# 02_Power.net
KiCad netlist of a schematic drawn in Altium Designer
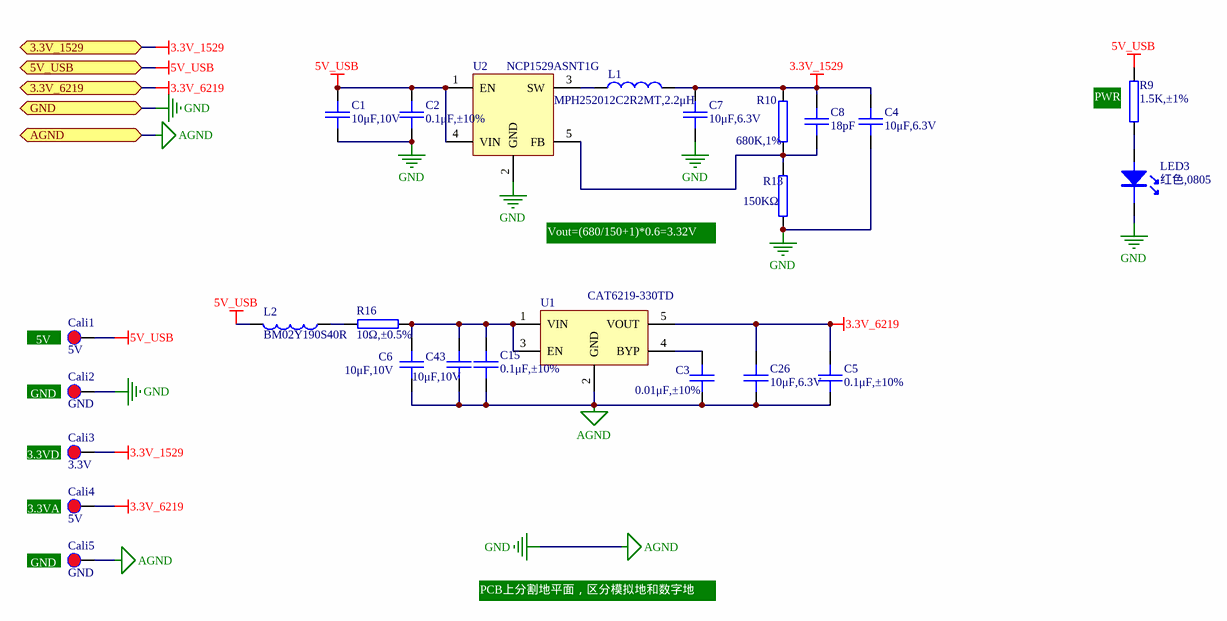
[diagram p0: 02.Power.SchDoc]

(export (version "E")
  (design (tool "Eeschema 10.0.6"))
  (components
    (comp (ref "C1")
      (value "10μF,10V")
      (footprint "0805C")
      (description "10μF,±10%,10V,X7R,GRM21BR71A106KE51L,0805,muRata,RoHS")
      (libsource (lib "ErpMaterialData") (part "CAP1"))
    )
    (comp (ref "C2")
      (value "0.1μF,±10%")
      (footprint "0402C")
      (description "GRM155R71C104KA88D,0.1μF,±10%,16V,X7R,0402,muRata,RoHS")
      (libsource (lib "ErpMaterialData") (part "CAP1"))
    )
    (comp (ref "C3")
      (value "0.01μF,±10%")
      (footprint "0402C")
      (description "GRM155R71H103KA88D,0.01μF,±10%,50V,X7R,0402,muRata,RoHS")
      (libsource (lib "ErpMaterialData") (part "CAP1"))
    )
    (comp (ref "C4")
      (value "10μF,6.3V")
      (footprint "0603C")
      (description "10μF,6.3V,X5R,GRM188R60J106M****,0603,Murata,RoHS")
      (libsource (lib "ErpMaterialData") (part "CAP1"))
    )
    (comp (ref "C5")
      (value "0.1μF,±10%")
      (footprint "0402C")
      (description "GRM155R71C104KA88D,0.1μF,±10%,16V,X7R,0402,muRata,RoHS")
      (libsource (lib "ErpMaterialData") (part "CAP1"))
    )
    (comp (ref "C6")
      (value "10μF,10V")
      (footprint "0805C")
      (description "10μF,±10%,10V,X7R,GRM21BR71A106KE51L,0805,muRata,RoHS")
      (libsource (lib "ErpMaterialData") (part "CAP1"))
    )
    (comp (ref "C7")
      (value "10μF,6.3V")
      (footprint "0603C")
      (description "10μF,6.3V,X5R,GRM188R60J106M****,0603,Murata,RoHS")
      (libsource (lib "ErpMaterialData") (part "CAP1"))
    )
    (comp (ref "C8")
      (value "18pF")
      (footprint "0402C")
      (description "GRM1555C1H180JA01D,18pF,±5%,50V,C0G,0402,muRata,RoHS")
      (libsource (lib "ErpMaterialData") (part "CAP1"))
    )
    (comp (ref "C15")
      (value "0.1μF,±10%")
      (footprint "0402C")
      (description "GRM155R71C104KA88D,0.1μF,±10%,16V,X7R,0402,muRata,RoHS")
      (libsource (lib "ErpMaterialData") (part "CAP1"))
    )
    (comp (ref "C26")
      (value "10μF,6.3V")
      (footprint "0603C")
      (description "10μF,6.3V,X5R,GRM188R60J106M****,0603,Murata,RoHS")
      (libsource (lib "ErpMaterialData") (part "CAP1"))
    )
    (comp (ref "C43")
      (value "10μF,10V")
      (footprint "0805C")
      (description "10μF,±10%,10V,X7R,GRM21BR71A106KE51L,0805,muRata,RoHS")
      (libsource (lib "ErpMaterialData") (part "CAP1"))
    )
    (comp (ref "Cali1") (value "5V") (footprint "PAD-25/40") (libsource (lib "无需物料号元件") (part "TEST-DOT")))
    (comp (ref "Cali2") (value "GND") (footprint "PAD-25/40") (libsource (lib "无需物料号元件") (part "TEST-DOT")))
    (comp (ref "Cali3") (value "3.3V") (footprint "PAD-25/40") (libsource (lib "无需物料号元件") (part "TEST-DOT")))
    (comp (ref "Cali4") (value "5V") (footprint "PAD-25/40") (libsource (lib "无需物料号元件") (part "TEST-DOT")))
    (comp (ref "Cali5") (value "GND") (footprint "PAD-25/40") (libsource (lib "无需物料号元件") (part "TEST-DOT")))
    (comp (ref "L1")
      (value "MPH252012C2R2MT,2.2μH")
      (footprint "INDC2520X10N")
      (description "MPH252012C2R2MT,2.2μH,±20%,700mA,1008,Sunlord,RoHs")
      (libsource (lib "ErpMaterialData") (part "INDUCTOR1"))
    )
    (comp (ref "L2")
      (value "BM02Y190S40R")
      (footprint "0402RL")
      (description "BM02Y190S40R,0402,丰晶,RoHS")
      (libsource (lib "ErpMaterialData") (part "INDUCTOR1"))
    )
    (comp (ref "LED3")
      (value "红色,0805")
      (footprint "LED-0805")
      (description "红色,0805,0805,RoHS")
      (fields (field (name "Comment") "LED1"))
      (libsource (lib "ErpMaterialData") (part "LED1"))
    )
    (comp (ref "R9")
      (value "1.5K,±1%")
      (footprint "0402R")
      (description "1.5K,±1%,0402,RALEC,RoHS")
      (libsource (lib "ErpMaterialData") (part "RES2"))
    )
    (comp (ref "R10")
      (value "680K,1%")
      (footprint "0402R")
      (description "680K,1%,0402,Ralec,RoHS")
      (libsource (lib "ErpMaterialData") (part "RES2"))
    )
    (comp (ref "R13")
      (value "150KΩ")
      (footprint "0603R")
      (description "150KΩ,0603,*,RoHS")
      (libsource (lib "ErpMaterialData") (part "RES2"))
    )
    (comp (ref "R16")
      (value "10Ω,±0.5%")
      (footprint "0402R")
      (description "10Ω,±0.5%,0402,RoHS")
      (libsource (lib "ErpMaterialData") (part "RES2"))
    )
    (comp (ref "U1")
      (value "CAT6219-330TD")
      (footprint "SOT-23-5")
      (description "CAT6219-330TD,TSOT-23-5,ON,RoHS")
      (libsource (lib "ErpMaterialData") (part "CAT6219"))
    )
    (comp (ref "U2")
      (value "NCP1529ASNT1G")
      (footprint "SOT-23-5")
      (description "NCP1529ASNT1G,TSOP-5,ON,RoHS")
      (libsource (lib "ErpMaterialData") (part "SCY99090SNT1G"))
    )
  )
  (nets
    (net (code "1") (name "3.3V_1529") (class "Default")
      (node (ref "C4") (pin "1") (pinfunction "1_1") (pintype "passive"))
      (node (ref "C7") (pin "1") (pinfunction "1_1") (pintype "passive"))
      (node (ref "C8") (pin "1") (pinfunction "1_1") (pintype "passive"))
      (node (ref "Cali3") (pin "1") (pinfunction "1_1") (pintype "passive"))
      (node (ref "L1") (pin "2") (pinfunction "2_2") (pintype "passive"))
      (node (ref "R10") (pin "2") (pinfunction "2_2") (pintype "passive"))
    )
    (net (code "2") (name "3.3V_6219") (class "Default")
      (node (ref "C26") (pin "1") (pinfunction "1_1") (pintype "passive"))
      (node (ref "C5") (pin "1") (pinfunction "1_1") (pintype "passive"))
      (node (ref "Cali4") (pin "1") (pinfunction "1_1") (pintype "passive"))
      (node (ref "U1") (pin "5") (pinfunction "VOUT_5") (pintype "passive"))
    )
    (net (code "3") (name "5V_USB") (class "Default")
      (node (ref "C1") (pin "1") (pinfunction "1_1") (pintype "passive"))
      (node (ref "C2") (pin "1") (pinfunction "1_1") (pintype "passive"))
      (node (ref "Cali1") (pin "1") (pinfunction "1_1") (pintype "passive"))
      (node (ref "L2") (pin "2") (pinfunction "2_2") (pintype "passive"))
      (node (ref "R9") (pin "2") (pinfunction "2_2") (pintype "passive"))
      (node (ref "U2") (pin "1") (pinfunction "EN_1") (pintype "passive"))
      (node (ref "U2") (pin "4") (pinfunction "VIN_4") (pintype "passive"))
    )
    (net (code "4") (name "AGND") (class "Default")
      (node (ref "C1") (pin "2") (pinfunction "2_2") (pintype "passive"))
      (node (ref "C15") (pin "2") (pinfunction "2_2") (pintype "passive"))
      (node (ref "C2") (pin "2") (pinfunction "2_2") (pintype "passive"))
      (node (ref "C26") (pin "2") (pinfunction "2_2") (pintype "passive"))
      (node (ref "C3") (pin "2") (pinfunction "2_2") (pintype "passive"))
      (node (ref "C4") (pin "2") (pinfunction "2_2") (pintype "passive"))
      (node (ref "C43") (pin "2") (pinfunction "2_2") (pintype "passive"))
      (node (ref "C5") (pin "2") (pinfunction "2_2") (pintype "passive"))
      (node (ref "C6") (pin "2") (pinfunction "2_2") (pintype "passive"))
      (node (ref "C7") (pin "2") (pinfunction "2_2") (pintype "passive"))
      (node (ref "Cali2") (pin "1") (pinfunction "1_1") (pintype "passive"))
      (node (ref "Cali5") (pin "1") (pinfunction "1_1") (pintype "passive"))
      (node (ref "LED3") (pin "2") (pinfunction "2_2") (pintype "passive"))
      (node (ref "R13") (pin "1") (pinfunction "1_1") (pintype "passive"))
      (node (ref "U1") (pin "2") (pinfunction "GND_2") (pintype "passive"))
      (node (ref "U2") (pin "2") (pinfunction "GND_2") (pintype "passive"))
    )
    (net (code "5") (name "Net-(L2-Pad1)") (class "Default")
      (node (ref "L2") (pin "1") (pinfunction "1_1") (pintype "passive"))
      (node (ref "R16") (pin "1") (pinfunction "1_1") (pintype "passive"))
    )
    (net (code "6") (name "Net-(LED3-Pad1)") (class "Default")
      (node (ref "LED3") (pin "1") (pinfunction "1_1") (pintype "passive"))
      (node (ref "R9") (pin "1") (pinfunction "1_1") (pintype "passive"))
    )
    (net (code "7") (name "Net-(U1-BYP)") (class "Default")
      (node (ref "C3") (pin "1") (pinfunction "1_1") (pintype "passive"))
      (node (ref "U1") (pin "4") (pinfunction "BYP_4") (pintype "passive"))
    )
    (net (code "8") (name "Net-(U1-EN)") (class "Default")
      (node (ref "C15") (pin "1") (pinfunction "1_1") (pintype "passive"))
      (node (ref "C43") (pin "1") (pinfunction "1_1") (pintype "passive"))
      (node (ref "C6") (pin "1") (pinfunction "1_1") (pintype "passive"))
      (node (ref "R16") (pin "2") (pinfunction "2_2") (pintype "passive"))
      (node (ref "U1") (pin "1") (pinfunction "VIN_1") (pintype "passive"))
      (node (ref "U1") (pin "3") (pinfunction "EN_3") (pintype "passive"))
    )
    (net (code "9") (name "Net-(U2-FB)") (class "Default")
      (node (ref "C8") (pin "2") (pinfunction "2_2") (pintype "passive"))
      (node (ref "R10") (pin "1") (pinfunction "1_1") (pintype "passive"))
      (node (ref "R13") (pin "2") (pinfunction "2_2") (pintype "passive"))
      (node (ref "U2") (pin "5") (pinfunction "FB_5") (pintype "passive"))
    )
    (net (code "10") (name "Net-(U2-SW)") (class "Default")
      (node (ref "L1") (pin "1") (pinfunction "1_1") (pintype "passive"))
      (node (ref "U2") (pin "3") (pinfunction "SW_3") (pintype "passive"))
    )
  )
)
